# sensorNode1.net
KiCad netlist of a schematic drawn in EAGLE
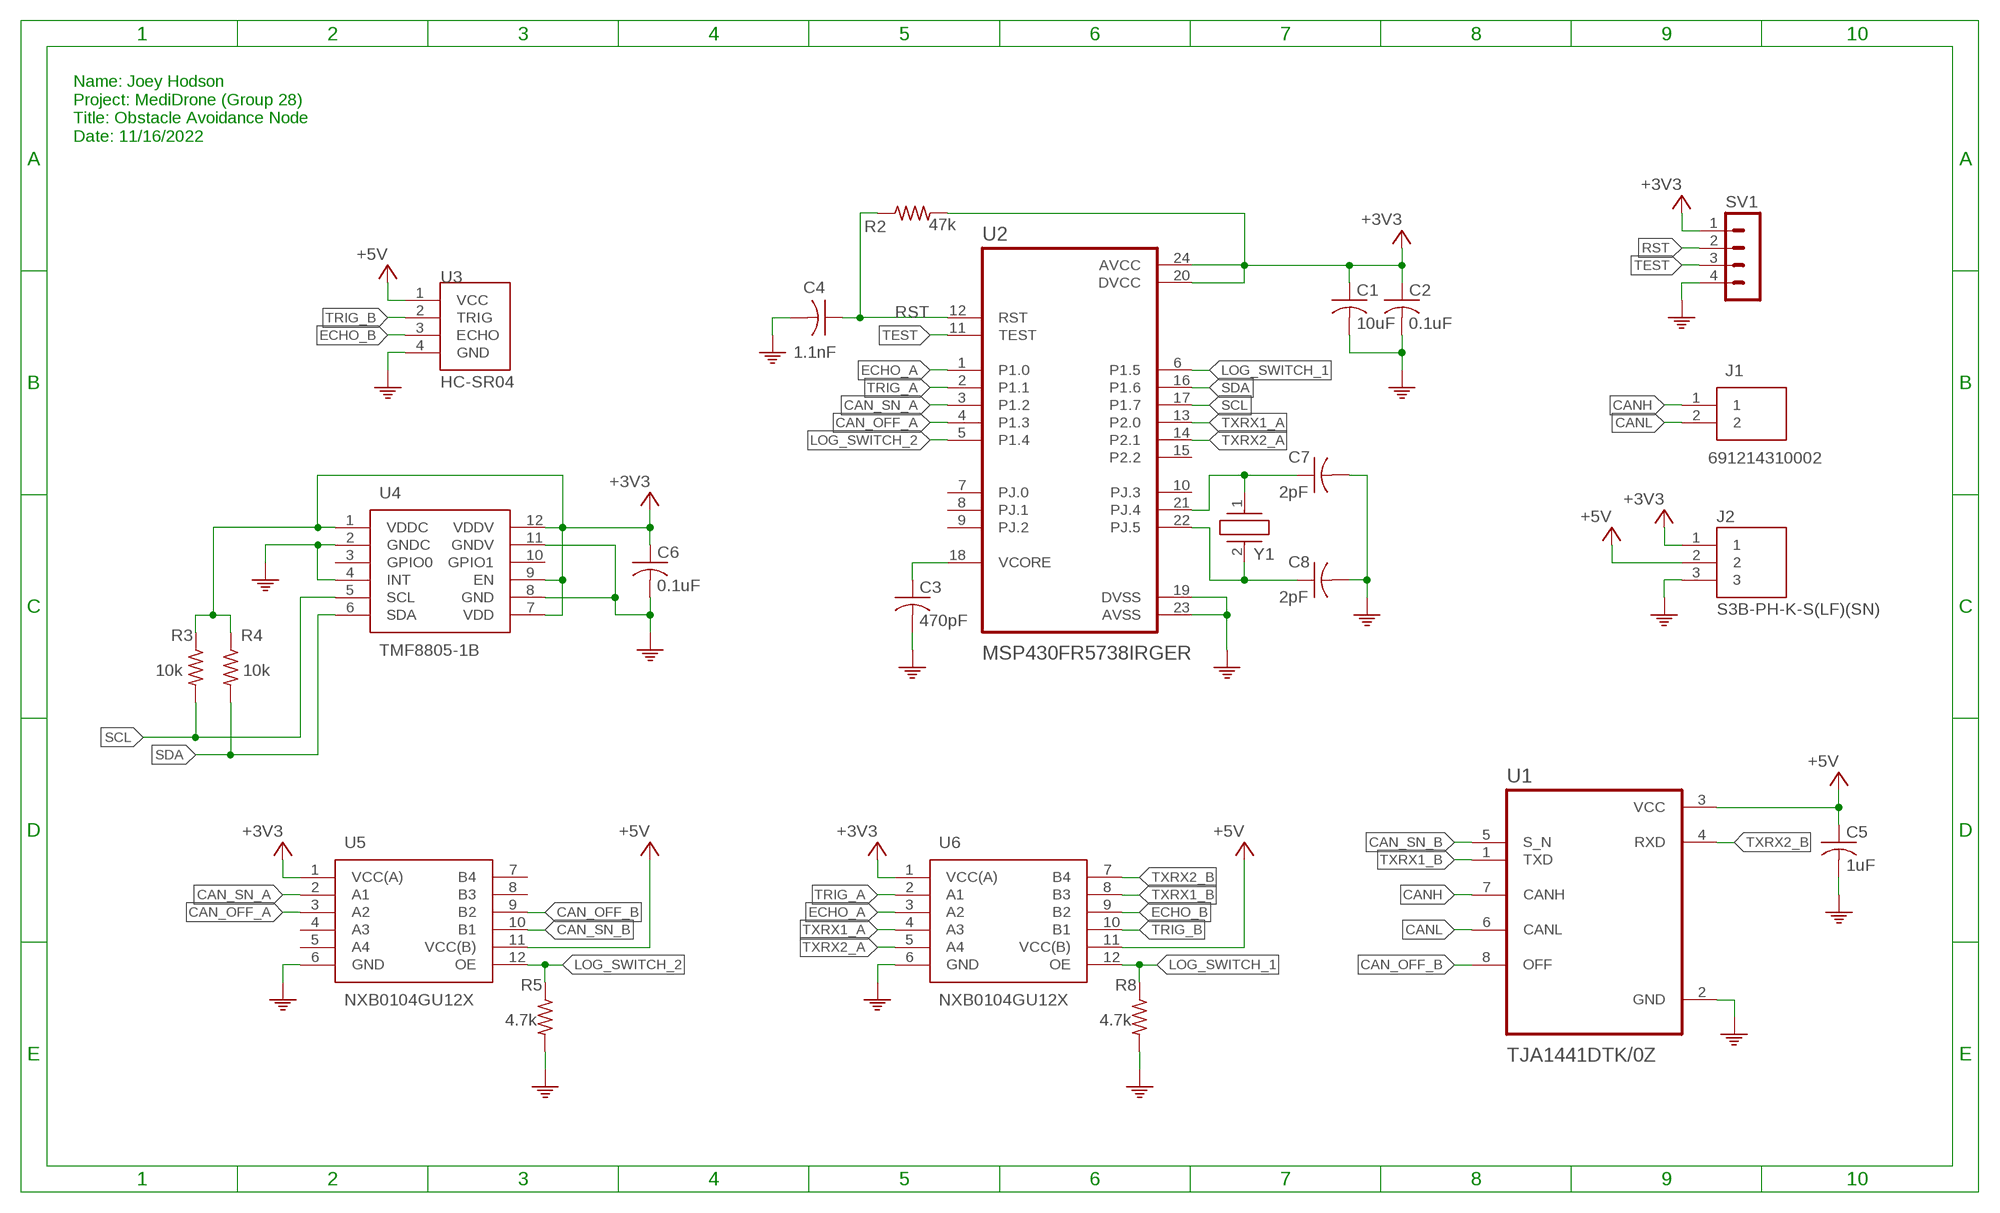
[diagram p0: schematic, sheet 1]

(export (version "E")
  (design (tool "Eeschema 10.0.6"))
  (components
    (comp (ref "C1")
      (value "10uF")
      (footprint "eagle-import:C0805")
      (libsource (lib "eagle-import") (part "C-USC0805"))
    )
    (comp (ref "C2")
      (value "0.1uF")
      (footprint "eagle-import:C0603")
      (libsource (lib "eagle-import") (part "C-USC0603"))
    )
    (comp (ref "C3")
      (value "470pF")
      (footprint "eagle-import:C0603")
      (libsource (lib "eagle-import") (part "C-USC0603"))
    )
    (comp (ref "C4")
      (value "1.1nF")
      (footprint "eagle-import:C0603")
      (libsource (lib "eagle-import") (part "C-USC0603"))
    )
    (comp (ref "C5")
      (value "1uF")
      (footprint "eagle-import:C0603")
      (libsource (lib "eagle-import") (part "C-USC0603"))
    )
    (comp (ref "C6")
      (value "0.1uF")
      (footprint "eagle-import:C0603")
      (libsource (lib "eagle-import") (part "C-USC0603"))
    )
    (comp (ref "C7")
      (value "2pF")
      (footprint "eagle-import:C0603")
      (libsource (lib "eagle-import") (part "C-USC0603"))
    )
    (comp (ref "C8")
      (value "2pF")
      (footprint "eagle-import:C0603")
      (libsource (lib "eagle-import") (part "C-USC0603"))
    )
    (comp (ref "J1")
      (value "691214310002")
      (footprint "eagle-import:SHDR2W90P0X381_1X2_802X740X850")
      (fields (field (name "MOUSER_PART_NUMBER") "710-691214310002"))
      (libsource (lib "eagle-import") (part "691214310002"))
    )
    (comp (ref "J2")
      (value "S3B-PH-K-S(LF)(SN)")
      (footprint "eagle-import:JST_S3B-PH-K-S(LF)(SN)")
      (fields (field (name "MF") "JST Sales"))
      (libsource (lib "eagle-import") (part "S3B-PH-K-S(LF)(SN)"))
    )
    (comp (ref "R2")
      (value "47k")
      (footprint "eagle-import:R0603")
      (libsource (lib "eagle-import") (part "R-US_R0603"))
    )
    (comp (ref "R3")
      (value "10k")
      (footprint "eagle-import:R0603")
      (libsource (lib "eagle-import") (part "R-US_R0603"))
    )
    (comp (ref "R4")
      (value "10k")
      (footprint "eagle-import:R0603")
      (libsource (lib "eagle-import") (part "R-US_R0603"))
    )
    (comp (ref "R5")
      (value "4.7k")
      (footprint "eagle-import:R0603")
      (libsource (lib "eagle-import") (part "R-US_R0603"))
    )
    (comp (ref "R8")
      (value "4.7k")
      (footprint "eagle-import:R0603")
      (libsource (lib "eagle-import") (part "R-US_R0603"))
    )
    (comp (ref "SV1")
      (value "MA04-1")
      (footprint "eagle-import:MA04-1")
      (libsource (lib "eagle-import") (part "MA04-1"))
    )
    (comp (ref "U1")
      (value "TJA1441DTK/0Z")
      (footprint "eagle-import:SON65P300X300X95-8N")
      (fields (field (name "MF") "NXP USA Inc."))
      (libsource (lib "eagle-import") (part "TJA1441DTK/0Z"))
    )
    (comp (ref "U2")
      (value "MSP430FR5738IRGER")
      (footprint "eagle-import:QFN50P400X400X100-25N")
      (fields (field (name "MF") "Texas Instruments"))
      (libsource (lib "eagle-import") (part "MSP430FR5738IRGER"))
    )
    (comp (ref "U3")
      (value "HC-SR04")
      (footprint "eagle-import:HC-SR04_VARIANT")
      (fields (field (name "MF") "OSEPP Electronics"))
      (libsource (lib "eagle-import") (part "HC-SR04"))
    )
    (comp (ref "U4")
      (value "TMF8805-1B")
      (footprint "eagle-import:TMF88051B")
      (fields (field (name "MOUSER_PART_NUMBER") "985-TMF8805-1B"))
      (libsource (lib "eagle-import") (part "TMF8805-1B"))
    )
    (comp (ref "U5")
      (value "NXB0104GU12X")
      (footprint "eagle-import:NXB0104GU12X")
      (fields (field (name "MOUSER_PART_NUMBER") "771-NXB0104GU12X"))
      (libsource (lib "eagle-import") (part "NXB0104GU12X"))
    )
    (comp (ref "U6")
      (value "NXB0104GU12X")
      (footprint "eagle-import:NXB0104GU12X")
      (fields (field (name "MOUSER_PART_NUMBER") "771-NXB0104GU12X"))
      (libsource (lib "eagle-import") (part "NXB0104GU12X"))
    )
    (comp (ref "Y1")
      (value "HC-49_U-S16000000ABJB")
      (footprint "eagle-import:HC49")
      (fields
        (field (name "MANUFACTURER_PART_NUMBER") "HC-49/U-S16000000ABJB")
        (field (name "MOUSER_PART_NUMBER") "695-HC49US16.0ABJB")
      )
      (libsource (lib "eagle-import") (part "HC-49_U-S16000000ABJB"))
    )
  )
  (nets
    (net (code "1") (name "+3V3") (class "Default")
      (node (ref "C1") (pin "1") (pinfunction "1_1") (pintype "passive"))
      (node (ref "C2") (pin "1") (pinfunction "1_1") (pintype "passive"))
      (node (ref "C6") (pin "1") (pinfunction "1_1") (pintype "passive"))
      (node (ref "J2") (pin "1") (pinfunction "1_1") (pintype "passive"))
      (node (ref "R2") (pin "2") (pinfunction "2_2") (pintype "passive"))
      (node (ref "R3") (pin "1") (pinfunction "1_1") (pintype "passive"))
      (node (ref "R4") (pin "1") (pinfunction "1_1") (pintype "passive"))
      (node (ref "SV1") (pin "1") (pinfunction "1_1") (pintype "passive"))
      (node (ref "U2") (pin "20") (pinfunction "DVCC_20") (pintype "power_in"))
      (node (ref "U2") (pin "24") (pinfunction "AVCC_24") (pintype "power_in"))
      (node (ref "U4") (pin "1") (pinfunction "VDDC_1") (pintype "bidirectional"))
      (node (ref "U4") (pin "12") (pinfunction "VDDV_12") (pintype "bidirectional"))
      (node (ref "U4") (pin "7") (pinfunction "VDD_7") (pintype "bidirectional"))
      (node (ref "U4") (pin "9") (pinfunction "EN_9") (pintype "bidirectional"))
      (node (ref "U5") (pin "1") (pinfunction "VCC(A)_1") (pintype "bidirectional"))
      (node (ref "U6") (pin "1") (pinfunction "VCC(A)_1") (pintype "bidirectional"))
    )
    (net (code "2") (name "+5V") (class "Default")
      (node (ref "C5") (pin "1") (pinfunction "1_1") (pintype "passive"))
      (node (ref "J2") (pin "2") (pinfunction "2_2") (pintype "passive"))
      (node (ref "U1") (pin "3") (pinfunction "VCC_3") (pintype "power_in"))
      (node (ref "U3") (pin "1") (pinfunction "VCC_1") (pintype "power_in"))
      (node (ref "U5") (pin "11") (pinfunction "VCC(B)_11") (pintype "bidirectional"))
      (node (ref "U6") (pin "11") (pinfunction "VCC(B)_11") (pintype "bidirectional"))
    )
    (net (code "3") (name "CANH") (class "Default")
      (node (ref "J1") (pin "1") (pinfunction "1_1") (pintype "bidirectional"))
      (node (ref "U1") (pin "7") (pinfunction "CANH_7") (pintype "bidirectional"))
    )
    (net (code "4") (name "CANL") (class "Default")
      (node (ref "J1") (pin "2") (pinfunction "2_2") (pintype "bidirectional"))
      (node (ref "U1") (pin "6") (pinfunction "CANL_6") (pintype "bidirectional"))
    )
    (net (code "5") (name "CAN_OFF_A") (class "Default")
      (node (ref "U2") (pin "4") (pinfunction "P1.3_4") (pintype "bidirectional"))
      (node (ref "U5") (pin "3") (pinfunction "A2_3") (pintype "bidirectional"))
    )
    (net (code "6") (name "CAN_OFF_B") (class "Default")
      (node (ref "U1") (pin "8") (pinfunction "OFF_8") (pintype "bidirectional"))
      (node (ref "U5") (pin "9") (pinfunction "B2_9") (pintype "bidirectional"))
    )
    (net (code "7") (name "CAN_SN_A") (class "Default")
      (node (ref "U2") (pin "3") (pinfunction "P1.2_3") (pintype "bidirectional"))
      (node (ref "U5") (pin "2") (pinfunction "A1_2") (pintype "bidirectional"))
    )
    (net (code "8") (name "CAN_SN_B") (class "Default")
      (node (ref "U1") (pin "5") (pinfunction "S_N_5") (pintype "input"))
      (node (ref "U5") (pin "10") (pinfunction "B1_10") (pintype "bidirectional"))
    )
    (net (code "9") (name "ECHO_A") (class "Default")
      (node (ref "U2") (pin "1") (pinfunction "P1.0_1") (pintype "bidirectional"))
      (node (ref "U6") (pin "3") (pinfunction "A2_3") (pintype "bidirectional"))
    )
    (net (code "10") (name "ECHO_B") (class "Default")
      (node (ref "U3") (pin "3") (pinfunction "ECHO_3") (pintype "bidirectional"))
      (node (ref "U6") (pin "9") (pinfunction "B2_9") (pintype "bidirectional"))
    )
    (net (code "11") (name "LOG_SWITCH_1") (class "Default")
      (node (ref "R8") (pin "1") (pinfunction "1_1") (pintype "passive"))
      (node (ref "U2") (pin "6") (pinfunction "P1.5_6") (pintype "bidirectional"))
      (node (ref "U6") (pin "12") (pinfunction "OE_12") (pintype "bidirectional"))
    )
    (net (code "12") (name "LOG_SWITCH_2") (class "Default")
      (node (ref "R5") (pin "1") (pinfunction "1_1") (pintype "passive"))
      (node (ref "U2") (pin "5") (pinfunction "P1.4_5") (pintype "bidirectional"))
      (node (ref "U5") (pin "12") (pinfunction "OE_12") (pintype "bidirectional"))
    )
    (net (code "13") (name "Net-(U2-PJ.4)") (class "Default")
      (node (ref "C7") (pin "1") (pinfunction "1_1") (pintype "passive"))
      (node (ref "U2") (pin "21") (pinfunction "PJ.4_21") (pintype "bidirectional"))
      (node (ref "Y1") (pin "1") (pinfunction "1_1") (pintype "bidirectional"))
    )
    (net (code "14") (name "Net-(U2-PJ.5)") (class "Default")
      (node (ref "C8") (pin "1") (pinfunction "1_1") (pintype "passive"))
      (node (ref "U2") (pin "22") (pinfunction "PJ.5_22") (pintype "bidirectional"))
      (node (ref "Y1") (pin "2") (pinfunction "2_2") (pintype "bidirectional"))
    )
    (net (code "15") (name "Net-(U2-VCORE)") (class "Default")
      (node (ref "C3") (pin "1") (pinfunction "1_1") (pintype "passive"))
      (node (ref "U2") (pin "18") (pinfunction "VCORE_18") (pintype "bidirectional"))
    )
    (net (code "16") (name "PE") (class "Default")
      (node (ref "C1") (pin "2") (pinfunction "2_2") (pintype "passive"))
      (node (ref "C2") (pin "2") (pinfunction "2_2") (pintype "passive"))
      (node (ref "C3") (pin "2") (pinfunction "2_2") (pintype "passive"))
      (node (ref "C4") (pin "2") (pinfunction "2_2") (pintype "passive"))
      (node (ref "C5") (pin "2") (pinfunction "2_2") (pintype "passive"))
      (node (ref "C6") (pin "2") (pinfunction "2_2") (pintype "passive"))
      (node (ref "C7") (pin "2") (pinfunction "2_2") (pintype "passive"))
      (node (ref "C8") (pin "2") (pinfunction "2_2") (pintype "passive"))
      (node (ref "J2") (pin "3") (pinfunction "3_3") (pintype "passive"))
      (node (ref "R5") (pin "2") (pinfunction "2_2") (pintype "passive"))
      (node (ref "R8") (pin "2") (pinfunction "2_2") (pintype "passive"))
      (node (ref "SV1") (pin "4") (pinfunction "4_4") (pintype "passive"))
      (node (ref "U1") (pin "2") (pinfunction "GND_2") (pintype "power_in"))
      (node (ref "U2") (pin "19") (pinfunction "DVSS_19") (pintype "power_in"))
      (node (ref "U2") (pin "23") (pinfunction "AVSS_23") (pintype "power_in"))
      (node (ref "U3") (pin "4") (pinfunction "GND_4") (pintype "power_in"))
      (node (ref "U4") (pin "11") (pinfunction "GNDV_11") (pintype "bidirectional"))
      (node (ref "U4") (pin "2") (pinfunction "GNDC_2") (pintype "bidirectional"))
      (node (ref "U4") (pin "4") (pinfunction "INT_4") (pintype "bidirectional"))
      (node (ref "U4") (pin "8") (pinfunction "GND_8") (pintype "bidirectional"))
      (node (ref "U5") (pin "6") (pinfunction "GND_6") (pintype "bidirectional"))
      (node (ref "U6") (pin "6") (pinfunction "GND_6") (pintype "bidirectional"))
    )
    (net (code "17") (name "RST") (class "Default")
      (node (ref "C4") (pin "1") (pinfunction "1_1") (pintype "passive"))
      (node (ref "R2") (pin "1") (pinfunction "1_1") (pintype "passive"))
      (node (ref "SV1") (pin "2") (pinfunction "2_2") (pintype "passive"))
      (node (ref "U2") (pin "12") (pinfunction "RST_12") (pintype "input"))
    )
    (net (code "18") (name "SCL") (class "Default")
      (node (ref "R3") (pin "2") (pinfunction "2_2") (pintype "passive"))
      (node (ref "U2") (pin "17") (pinfunction "P1.7_17") (pintype "bidirectional"))
      (node (ref "U4") (pin "5") (pinfunction "SCL_5") (pintype "bidirectional"))
    )
    (net (code "19") (name "SDA") (class "Default")
      (node (ref "R4") (pin "2") (pinfunction "2_2") (pintype "passive"))
      (node (ref "U2") (pin "16") (pinfunction "P1.6_16") (pintype "bidirectional"))
      (node (ref "U4") (pin "6") (pinfunction "SDA_6") (pintype "bidirectional"))
    )
    (net (code "20") (name "TEST") (class "Default")
      (node (ref "SV1") (pin "3") (pinfunction "3_3") (pintype "passive"))
      (node (ref "U2") (pin "11") (pinfunction "TEST_11") (pintype "input"))
    )
    (net (code "21") (name "TRIG_A") (class "Default")
      (node (ref "U2") (pin "2") (pinfunction "P1.1_2") (pintype "bidirectional"))
      (node (ref "U6") (pin "2") (pinfunction "A1_2") (pintype "bidirectional"))
    )
    (net (code "22") (name "TRIG_B") (class "Default")
      (node (ref "U3") (pin "2") (pinfunction "TRIG_2") (pintype "bidirectional"))
      (node (ref "U6") (pin "10") (pinfunction "B1_10") (pintype "bidirectional"))
    )
    (net (code "23") (name "TXRX1_A") (class "Default")
      (node (ref "U2") (pin "13") (pinfunction "P2.0_13") (pintype "bidirectional"))
      (node (ref "U6") (pin "4") (pinfunction "A3_4") (pintype "bidirectional"))
    )
    (net (code "24") (name "TXRX1_B") (class "Default")
      (node (ref "U1") (pin "1") (pinfunction "TXD_1") (pintype "input"))
      (node (ref "U6") (pin "8") (pinfunction "B3_8") (pintype "bidirectional"))
    )
    (net (code "25") (name "TXRX2_A") (class "Default")
      (node (ref "U2") (pin "14") (pinfunction "P2.1_14") (pintype "bidirectional"))
      (node (ref "U6") (pin "5") (pinfunction "A4_5") (pintype "bidirectional"))
    )
    (net (code "26") (name "TXRX2_B") (class "Default")
      (node (ref "U1") (pin "4") (pinfunction "RXD_4") (pintype "output"))
      (node (ref "U6") (pin "7") (pinfunction "B4_7") (pintype "bidirectional"))
    )
    (net (code "27") (name "unconnected-(U2-P2.2-Pad15)") (class "Default")
      (node (ref "U2") (pin "15") (pinfunction "P2.2_15") (pintype "bidirectional"))
    )
    (net (code "28") (name "unconnected-(U2-PJ.0-Pad7)") (class "Default")
      (node (ref "U2") (pin "7") (pinfunction "PJ.0_7") (pintype "bidirectional"))
    )
    (net (code "29") (name "unconnected-(U2-PJ.1-Pad8)") (class "Default")
      (node (ref "U2") (pin "8") (pinfunction "PJ.1_8") (pintype "bidirectional"))
    )
    (net (code "30") (name "unconnected-(U2-PJ.2-Pad9)") (class "Default")
      (node (ref "U2") (pin "9") (pinfunction "PJ.2_9") (pintype "bidirectional"))
    )
    (net (code "31") (name "unconnected-(U2-PJ.3-Pad10)") (class "Default")
      (node (ref "U2") (pin "10") (pinfunction "PJ.3_10") (pintype "bidirectional"))
    )
    (net (code "32") (name "unconnected-(U4-GPIO0-Pad3)") (class "Default")
      (node (ref "U4") (pin "3") (pinfunction "GPIO0_3") (pintype "bidirectional"))
    )
    (net (code "33") (name "unconnected-(U4-GPIO1-Pad10)") (class "Default")
      (node (ref "U4") (pin "10") (pinfunction "GPIO1_10") (pintype "bidirectional"))
    )
    (net (code "34") (name "unconnected-(U5-A3-Pad4)") (class "Default")
      (node (ref "U5") (pin "4") (pinfunction "A3_4") (pintype "bidirectional"))
    )
    (net (code "35") (name "unconnected-(U5-A4-Pad5)") (class "Default")
      (node (ref "U5") (pin "5") (pinfunction "A4_5") (pintype "bidirectional"))
    )
    (net (code "36") (name "unconnected-(U5-B3-Pad8)") (class "Default")
      (node (ref "U5") (pin "8") (pinfunction "B3_8") (pintype "bidirectional"))
    )
    (net (code "37") (name "unconnected-(U5-B4-Pad7)") (class "Default")
      (node (ref "U5") (pin "7") (pinfunction "B4_7") (pintype "bidirectional"))
    )
  )
)
